# Overview.net
KiCad netlist of a schematic drawn in Altium Designer
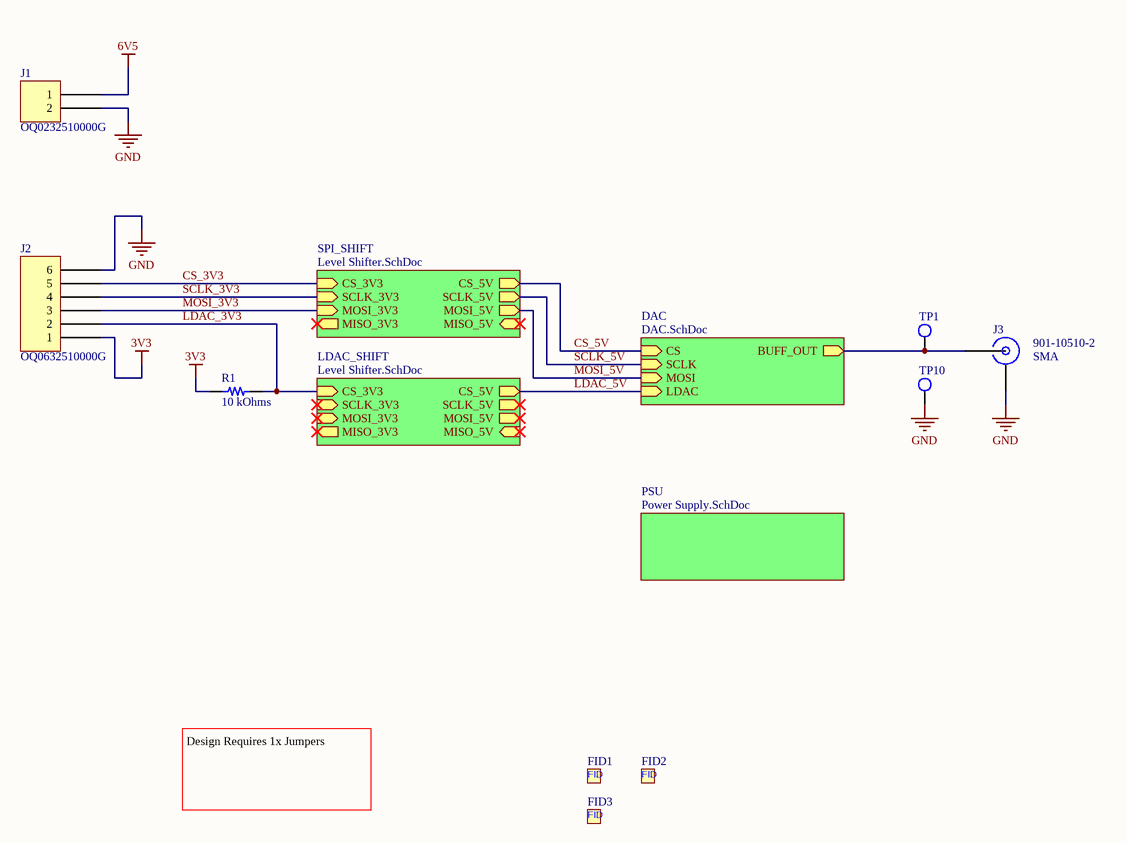
[diagram p0: Overview.SchDoc]

(export (version "E")
  (design (tool "Eeschema 10.0.6"))
  (components
    (comp (ref "FID1")
      (value "Fiducial")
      (footprint "Fiducial-1mm")
      (libsource (lib "Original Circuit") (part "Fiducial"))
    )
    (comp (ref "FID2")
      (value "Fiducial")
      (footprint "Fiducial-1mm")
      (libsource (lib "Original Circuit") (part "Fiducial"))
    )
    (comp (ref "FID3")
      (value "Fiducial")
      (footprint "Fiducial-1mm")
      (libsource (lib "Original Circuit") (part "Fiducial"))
    )
    (comp (ref "J1")
      (value "OQ0232510000G")
      (footprint "FCI 06-381-2PIN")
      (description "TERM BLOCK HDR 2POS 90DEG 3.81MM")
      (fields (field (name "MANUFACTURER") "Amphenol Anytek"))
      (libsource (lib "altiumlibrary.com") (part "2 Pin"))
    )
    (comp (ref "J2")
      (value "OQ0632510000G")
      (footprint "FCI 06-381-6PIN")
      (description "TERM BLOCK HDR 6POS 90DEG 3.81MM")
      (fields (field (name "MANUFACTURER") "Amphenol Anytek"))
      (libsource (lib "altiumlibrary.com") (part "6 Pin"))
    )
    (comp (ref "J3")
      (value "901-10510-2")
      (footprint "AMPHENOL 901-10510-2")
      (description "CONN SMA JACK R/A 50OHM EDGE MNT")
      (fields (field (name "CONNECTOR STYLE") "SMA") (field (name "MANUFACTURER") "Amphenol RF"))
      (libsource (lib "altiumlibrary.com") (part "COAXIAL JACK"))
    )
    (comp (ref "R1")
      (value "10 kOhms")
      (footprint "RES 0603_1608")
      (description "RES SMD 10K OHM 1% 1/10W 0603")
      (fields (field (name "PART NUMBER") "CR0603-FX-1002ELF") (field (name "MANUFACTURER") "Bourns Inc."))
      (libsource (lib "altiumlibrary.com") (part "Resistor"))
    )
    (comp (ref "TP1")
      (value "Test Point")
      (footprint "TestPoint-1.5mm")
      (libsource (lib "Original Circuit") (part "Test Point"))
    )
    (comp (ref "TP10")
      (value "Test Point")
      (footprint "TestPoint-1.5mm")
      (libsource (lib "Original Circuit") (part "Test Point"))
    )
  )
  (nets
    (net (code "1") (name "/BUFF_OUT") (class "Default")
      (node (ref "J3") (pin "S") (pinfunction "SIGNAL_S") (pintype "passive"))
      (node (ref "TP1") (pin "1") (pinfunction "TP_1") (pintype "passive"))
    )
    (net (code "2") (name "/CS_3V3") (class "Default")
      (node (ref "J2") (pin "5") (pinfunction "5_5") (pintype "passive"))
    )
    (net (code "4") (name "/LDAC_3V3") (class "Default")
      (node (ref "J2") (pin "2") (pinfunction "2_2") (pintype "passive"))
      (node (ref "R1") (pin "1") (pinfunction "1_1") (pintype "passive"))
    )
    (net (code "10") (name "/MOSI_3V3") (class "Default")
      (node (ref "J2") (pin "3") (pinfunction "3_3") (pintype "passive"))
    )
    (net (code "14") (name "/SCLK_3V3") (class "Default")
      (node (ref "J2") (pin "4") (pinfunction "4_4") (pintype "passive"))
    )
    (net (code "18") (name "3V3") (class "Default")
      (node (ref "J2") (pin "1") (pinfunction "1_1") (pintype "passive"))
      (node (ref "R1") (pin "2") (pinfunction "2_2") (pintype "passive"))
    )
    (net (code "19") (name "6V5") (class "Default")
      (node (ref "J1") (pin "1") (pinfunction "1_1") (pintype "passive"))
    )
    (net (code "20") (name "GND") (class "Default")
      (node (ref "J1") (pin "2") (pinfunction "2_2") (pintype "passive"))
      (node (ref "J2") (pin "6") (pinfunction "6_6") (pintype "passive"))
      (node (ref "J3") (pin "G") (pinfunction "GND_G") (pintype "passive"))
      (node (ref "TP10") (pin "1") (pinfunction "TP_1") (pintype "passive"))
    )
  )
)
